# expansion.net
KiCad netlist of a schematic drawn in EAGLE
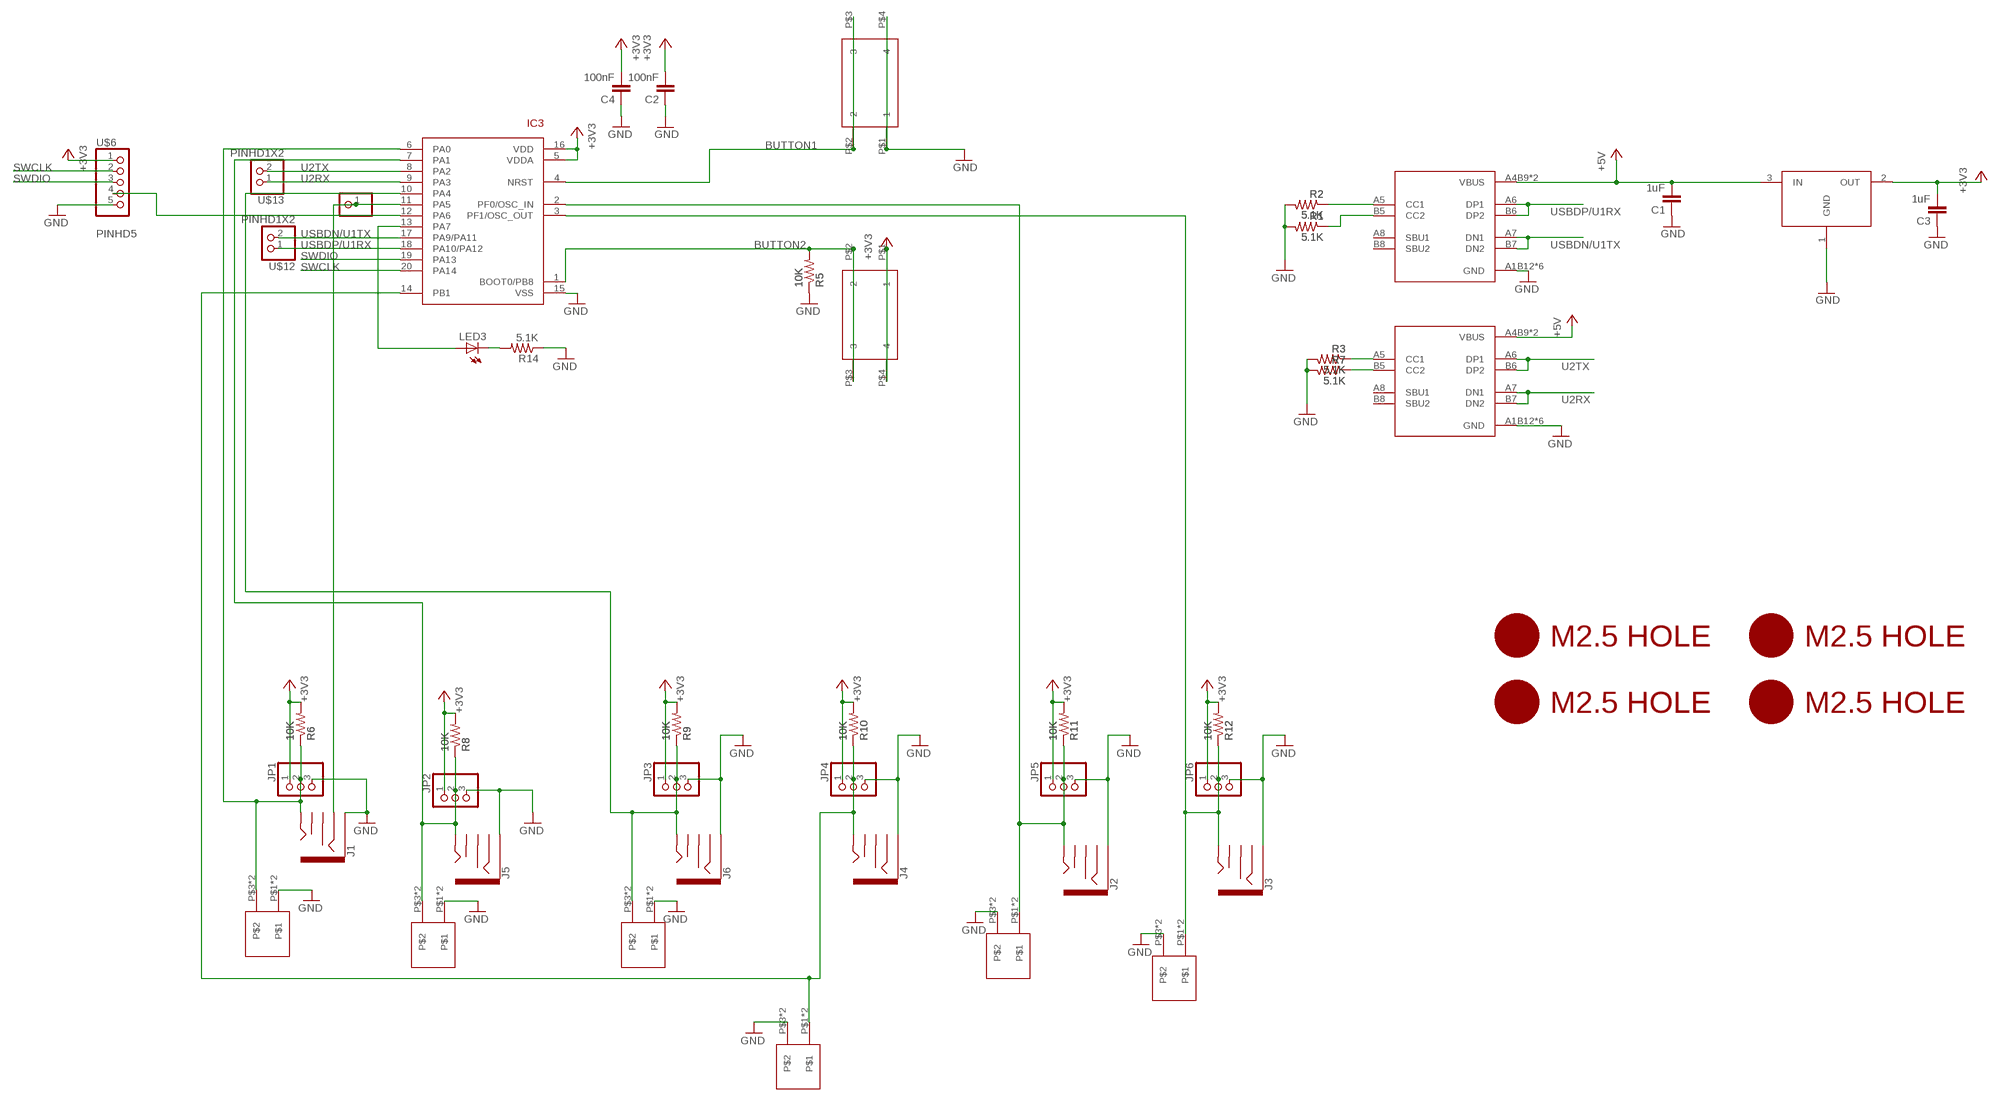
[diagram p0: schematic, sheet 1]

(export (version "E")
  (design (tool "Eeschema 10.0.6"))
  (components
    (comp (ref "C1")
      (value "1uF")
      (footprint "eagle-import:0805")
      (libsource (lib "eagle-import") (part "CAP0805"))
    )
    (comp (ref "C2")
      (value "100nF")
      (footprint "eagle-import:0805")
      (libsource (lib "eagle-import") (part "CAP0805"))
    )
    (comp (ref "C3")
      (value "1uF")
      (footprint "eagle-import:0805")
      (libsource (lib "eagle-import") (part "CAP0805"))
    )
    (comp (ref "C4")
      (value "100nF")
      (footprint "eagle-import:0805")
      (libsource (lib "eagle-import") (part "CAP0805"))
    )
    (comp (ref "IC3")
      (value "STM32F042F4")
      (footprint "eagle-import:TSSOP20")
      (libsource (lib "eagle-import") (part "STM32F042F4"))
    )
    (comp (ref "J1")
      (value "AUDIO_JACK_3.5MM_PTH")
      (footprint "eagle-import:AUDIO-JACK")
      (libsource (lib "eagle-import") (part "AUDIO_JACK_3.5MM_PTH"))
    )
    (comp (ref "J2")
      (value "AUDIO_JACK_3.5MM_PTH")
      (footprint "eagle-import:AUDIO-JACK")
      (libsource (lib "eagle-import") (part "AUDIO_JACK_3.5MM_PTH"))
    )
    (comp (ref "J3")
      (value "AUDIO_JACK_3.5MM_PTH")
      (footprint "eagle-import:AUDIO-JACK")
      (libsource (lib "eagle-import") (part "AUDIO_JACK_3.5MM_PTH"))
    )
    (comp (ref "J4")
      (value "AUDIO_JACK_3.5MM_PTH")
      (footprint "eagle-import:AUDIO-JACK")
      (libsource (lib "eagle-import") (part "AUDIO_JACK_3.5MM_PTH"))
    )
    (comp (ref "J5")
      (value "AUDIO_JACK_3.5MM_PTH")
      (footprint "eagle-import:AUDIO-JACK")
      (libsource (lib "eagle-import") (part "AUDIO_JACK_3.5MM_PTH"))
    )
    (comp (ref "J6")
      (value "AUDIO_JACK_3.5MM_PTH")
      (footprint "eagle-import:AUDIO-JACK")
      (libsource (lib "eagle-import") (part "AUDIO_JACK_3.5MM_PTH"))
    )
    (comp (ref "JP1")
      (value "PINHD-1X3")
      (footprint "eagle-import:1X03")
      (libsource (lib "eagle-import") (part "PINHD-1X3"))
    )
    (comp (ref "JP2")
      (value "PINHD-1X3")
      (footprint "eagle-import:1X03")
      (libsource (lib "eagle-import") (part "PINHD-1X3"))
    )
    (comp (ref "JP3")
      (value "PINHD-1X3")
      (footprint "eagle-import:1X03")
      (libsource (lib "eagle-import") (part "PINHD-1X3"))
    )
    (comp (ref "JP4")
      (value "PINHD-1X3")
      (footprint "eagle-import:1X03")
      (libsource (lib "eagle-import") (part "PINHD-1X3"))
    )
    (comp (ref "JP5")
      (value "PINHD-1X3")
      (footprint "eagle-import:1X03")
      (libsource (lib "eagle-import") (part "PINHD-1X3"))
    )
    (comp (ref "JP6")
      (value "PINHD-1X3")
      (footprint "eagle-import:1X03")
      (libsource (lib "eagle-import") (part "PINHD-1X3"))
    )
    (comp (ref "JP7")
      (value "PINHD-1X1CB")
      (footprint "eagle-import:1X01-CLEANBIG")
      (libsource (lib "eagle-import") (part "PINHD-1X1CB"))
    )
    (comp (ref "LED3")
      (value "LEDCHIP-LED0805")
      (footprint "eagle-import:CHIP-LED0805")
      (libsource (lib "eagle-import") (part "LEDCHIP-LED0805"))
    )
    (comp (ref "R1")
      (value "5.1K")
      (footprint "eagle-import:0805")
      (libsource (lib "eagle-import") (part "joyAnalog_RESISTOR0805-RES"))
    )
    (comp (ref "R2")
      (value "5.1K")
      (footprint "eagle-import:0805")
      (libsource (lib "eagle-import") (part "joyAnalog_RESISTOR0805-RES"))
    )
    (comp (ref "R3")
      (value "5.1K")
      (footprint "eagle-import:0805")
      (libsource (lib "eagle-import") (part "joyAnalog_RESISTOR0805-RES"))
    )
    (comp (ref "R5")
      (value "10K")
      (footprint "eagle-import:0805")
      (libsource (lib "eagle-import") (part "joyAnalog_RESISTOR0805-RES"))
    )
    (comp (ref "R6")
      (value "10K")
      (footprint "eagle-import:0805")
      (libsource (lib "eagle-import") (part "joyAnalog_RESISTOR0805-RES"))
    )
    (comp (ref "R7")
      (value "5.1K")
      (footprint "eagle-import:0805")
      (libsource (lib "eagle-import") (part "joyAnalog_RESISTOR0805-RES"))
    )
    (comp (ref "R8")
      (value "10K")
      (footprint "eagle-import:0805")
      (libsource (lib "eagle-import") (part "joyAnalog_RESISTOR0805-RES"))
    )
    (comp (ref "R9")
      (value "10K")
      (footprint "eagle-import:0805")
      (libsource (lib "eagle-import") (part "joyAnalog_RESISTOR0805-RES"))
    )
    (comp (ref "R10")
      (value "10K")
      (footprint "eagle-import:0805")
      (libsource (lib "eagle-import") (part "joyAnalog_RESISTOR0805-RES"))
    )
    (comp (ref "R11")
      (value "10K")
      (footprint "eagle-import:0805")
      (libsource (lib "eagle-import") (part "joyAnalog_RESISTOR0805-RES"))
    )
    (comp (ref "R12")
      (value "10K")
      (footprint "eagle-import:0805")
      (libsource (lib "eagle-import") (part "joyAnalog_RESISTOR0805-RES"))
    )
    (comp (ref "R14")
      (value "5.1K")
      (footprint "eagle-import:0805")
      (libsource (lib "eagle-import") (part "RESISTOR0805-RES"))
    )
    (comp (ref "SW3")
      (value "324_SW")
      (footprint "eagle-import:342_SWICH_FOOT")
      (libsource (lib "eagle-import") (part "324_SW"))
    )
    (comp (ref "SW4")
      (value "324_SW")
      (footprint "eagle-import:342_SWICH_FOOT")
      (libsource (lib "eagle-import") (part "324_SW"))
    )
    (comp (ref "U$1")
      (value "DG2204R-2")
      (footprint "eagle-import:DG2204R-2")
      (libsource (lib "eagle-import") (part "DG2204R-2"))
    )
    (comp (ref "U$2")
      (value "DG2204R-2")
      (footprint "eagle-import:DG2204R-2")
      (libsource (lib "eagle-import") (part "DG2204R-2"))
    )
    (comp (ref "U$3")
      (value "DG2204R-2")
      (footprint "eagle-import:DG2204R-2")
      (libsource (lib "eagle-import") (part "DG2204R-2"))
    )
    (comp (ref "U$4")
      (value "DG2204R-2")
      (footprint "eagle-import:DG2204R-2")
      (libsource (lib "eagle-import") (part "DG2204R-2"))
    )
    (comp (ref "U$5")
      (value "DG2204R-2")
      (footprint "eagle-import:DG2204R-2")
      (libsource (lib "eagle-import") (part "DG2204R-2"))
    )
    (comp (ref "U$6")
      (value "PINHD5")
      (footprint "eagle-import:1X05")
      (libsource (lib "eagle-import") (part "PINHD5"))
    )
    (comp (ref "U$7")
      (value "DG2204R-2")
      (footprint "eagle-import:DG2204R-2")
      (libsource (lib "eagle-import") (part "DG2204R-2"))
    )
    (comp (ref "U$8")
      (value "M2.5HOLE")
      (footprint "eagle-import:M2.5HOLE")
      (libsource (lib "eagle-import") (part "M2.5HOLE"))
    )
    (comp (ref "U$9")
      (value "M2.5HOLE")
      (footprint "eagle-import:M2.5HOLE")
      (libsource (lib "eagle-import") (part "M2.5HOLE"))
    )
    (comp (ref "U$10")
      (value "M2.5HOLE")
      (footprint "eagle-import:M2.5HOLE")
      (libsource (lib "eagle-import") (part "M2.5HOLE"))
    )
    (comp (ref "U$11")
      (value "M2.5HOLE")
      (footprint "eagle-import:M2.5HOLE")
      (libsource (lib "eagle-import") (part "M2.5HOLE"))
    )
    (comp (ref "U$12")
      (value "PINHD1X2")
      (footprint "eagle-import:1X02")
      (libsource (lib "eagle-import") (part "PINHD1X2"))
    )
    (comp (ref "U$13")
      (value "PINHD1X2")
      (footprint "eagle-import:1X02")
      (libsource (lib "eagle-import") (part "PINHD1X2"))
    )
    (comp (ref "U1")
      (value "USBC_16P")
      (footprint "eagle-import:USBC_16P_FOOT")
      (libsource (lib "eagle-import") (part "USBC_16P"))
    )
    (comp (ref "U2")
      (value "USBC_16P")
      (footprint "eagle-import:USBC_16P_FOOT")
      (libsource (lib "eagle-import") (part "USBC_16P"))
    )
    (comp (ref "U4")
      (value "XC6206_DEV")
      (footprint "eagle-import:SOT23R_INFINEON")
      (libsource (lib "eagle-import") (part "XC6206_DEV"))
    )
  )
  (nets
    (net (code "1") (name "+3V3") (class "Default")
      (node (ref "C2") (pin "2") (pinfunction "2_2") (pintype "passive"))
      (node (ref "C3") (pin "2") (pinfunction "2_2") (pintype "passive"))
      (node (ref "C4") (pin "2") (pinfunction "2_2") (pintype "passive"))
      (node (ref "IC3") (pin "16") (pinfunction "VDD_16") (pintype "bidirectional"))
      (node (ref "IC3") (pin "5") (pinfunction "VDDA_5") (pintype "bidirectional"))
      (node (ref "JP1") (pin "1") (pinfunction "1_1") (pintype "passive"))
      (node (ref "JP2") (pin "1") (pinfunction "1_1") (pintype "passive"))
      (node (ref "JP3") (pin "1") (pinfunction "1_1") (pintype "passive"))
      (node (ref "JP4") (pin "1") (pinfunction "1_1") (pintype "passive"))
      (node (ref "JP5") (pin "1") (pinfunction "1_1") (pintype "passive"))
      (node (ref "JP6") (pin "1") (pinfunction "1_1") (pintype "passive"))
      (node (ref "R10") (pin "2") (pinfunction "2_2") (pintype "passive"))
      (node (ref "R11") (pin "2") (pinfunction "2_2") (pintype "passive"))
      (node (ref "R12") (pin "2") (pinfunction "2_2") (pintype "passive"))
      (node (ref "R6") (pin "2") (pinfunction "2_2") (pintype "passive"))
      (node (ref "R8") (pin "2") (pinfunction "2_2") (pintype "passive"))
      (node (ref "R9") (pin "2") (pinfunction "2_2") (pintype "passive"))
      (node (ref "SW4") (pin "P$1") (pinfunction "1_P$1") (pintype "bidirectional"))
      (node (ref "SW4") (pin "P$4") (pinfunction "4_P$4") (pintype "bidirectional"))
      (node (ref "U$6") (pin "1") (pinfunction "1_1") (pintype "passive"))
      (node (ref "U4") (pin "2") (pinfunction "OUT_2") (pintype "bidirectional"))
    )
    (net (code "2") (name "+5V") (class "Default")
      (node (ref "C1") (pin "2") (pinfunction "2_2") (pintype "passive"))
      (node (ref "U1") (pin "A4B9") (pinfunction "VBUS_A4B9") (pintype "bidirectional"))
      (node (ref "U1") (pin "B4A9") (pinfunction "VBUS_B4A9") (pintype "bidirectional"))
      (node (ref "U2") (pin "A4B9") (pinfunction "VBUS_A4B9") (pintype "bidirectional"))
      (node (ref "U2") (pin "B4A9") (pinfunction "VBUS_B4A9") (pintype "bidirectional"))
      (node (ref "U4") (pin "3") (pinfunction "IN_3") (pintype "bidirectional"))
    )
    (net (code "3") (name "/BUTTON1") (class "Default")
      (node (ref "IC3") (pin "4") (pinfunction "NRST_4") (pintype "bidirectional"))
      (node (ref "SW3") (pin "P$2") (pinfunction "2_P$2") (pintype "bidirectional"))
      (node (ref "SW3") (pin "P$3") (pinfunction "3_P$3") (pintype "bidirectional"))
    )
    (net (code "4") (name "/BUTTON2") (class "Default")
      (node (ref "IC3") (pin "1") (pinfunction "BOOT0/PB8_1") (pintype "bidirectional"))
      (node (ref "R5") (pin "2") (pinfunction "2_2") (pintype "passive"))
      (node (ref "SW4") (pin "P$2") (pinfunction "2_P$2") (pintype "bidirectional"))
      (node (ref "SW4") (pin "P$3") (pinfunction "3_P$3") (pintype "bidirectional"))
    )
    (net (code "5") (name "/SWCLK") (class "Default")
      (node (ref "IC3") (pin "20") (pinfunction "PA14_20") (pintype "bidirectional"))
      (node (ref "U$6") (pin "2") (pinfunction "2_2") (pintype "passive"))
    )
    (net (code "6") (name "/SWDIO") (class "Default")
      (node (ref "IC3") (pin "19") (pinfunction "PA13_19") (pintype "bidirectional"))
      (node (ref "U$6") (pin "3") (pinfunction "3_3") (pintype "passive"))
    )
    (net (code "7") (name "/U2RX") (class "Default")
      (node (ref "IC3") (pin "9") (pinfunction "PA3_9") (pintype "bidirectional"))
      (node (ref "U$13") (pin "1") (pinfunction "1_1") (pintype "passive"))
      (node (ref "U1") (pin "A7") (pinfunction "DN1_A7") (pintype "bidirectional"))
      (node (ref "U1") (pin "B7") (pinfunction "DN2_B7") (pintype "bidirectional"))
    )
    (net (code "8") (name "/U2TX") (class "Default")
      (node (ref "IC3") (pin "8") (pinfunction "PA2_8") (pintype "bidirectional"))
      (node (ref "U$13") (pin "2") (pinfunction "2_2") (pintype "passive"))
      (node (ref "U1") (pin "A6") (pinfunction "DP1_A6") (pintype "bidirectional"))
      (node (ref "U1") (pin "B6") (pinfunction "DP2_B6") (pintype "bidirectional"))
    )
    (net (code "9") (name "/USBDN{slash}U1TX") (class "Default")
      (node (ref "IC3") (pin "17") (pinfunction "PA9/PA11_17") (pintype "bidirectional"))
      (node (ref "U$12") (pin "2") (pinfunction "2_2") (pintype "passive"))
      (node (ref "U2") (pin "A7") (pinfunction "DN1_A7") (pintype "bidirectional"))
      (node (ref "U2") (pin "B7") (pinfunction "DN2_B7") (pintype "bidirectional"))
    )
    (net (code "10") (name "/USBDP{slash}U1RX") (class "Default")
      (node (ref "IC3") (pin "18") (pinfunction "PA10/PA12_18") (pintype "bidirectional"))
      (node (ref "U$12") (pin "1") (pinfunction "1_1") (pintype "passive"))
      (node (ref "U2") (pin "A6") (pinfunction "DP1_A6") (pintype "bidirectional"))
      (node (ref "U2") (pin "B6") (pinfunction "DP2_B6") (pintype "bidirectional"))
    )
    (net (code "11") (name "GND") (class "Default")
      (node (ref "C1") (pin "1") (pinfunction "1_1") (pintype "passive"))
      (node (ref "C2") (pin "1") (pinfunction "1_1") (pintype "passive"))
      (node (ref "C3") (pin "1") (pinfunction "1_1") (pintype "passive"))
      (node (ref "C4") (pin "1") (pinfunction "1_1") (pintype "passive"))
      (node (ref "IC3") (pin "15") (pinfunction "VSS_15") (pintype "bidirectional"))
      (node (ref "J1") (pin "SLEEVE") (pinfunction "SLEEVE_SLEEVE") (pintype "bidirectional"))
      (node (ref "J2") (pin "SLEEVE") (pinfunction "SLEEVE_SLEEVE") (pintype "bidirectional"))
      (node (ref "J3") (pin "SLEEVE") (pinfunction "SLEEVE_SLEEVE") (pintype "bidirectional"))
      (node (ref "J4") (pin "SLEEVE") (pinfunction "SLEEVE_SLEEVE") (pintype "bidirectional"))
      (node (ref "J5") (pin "SLEEVE") (pinfunction "SLEEVE_SLEEVE") (pintype "bidirectional"))
      (node (ref "J6") (pin "SLEEVE") (pinfunction "SLEEVE_SLEEVE") (pintype "bidirectional"))
      (node (ref "JP1") (pin "3") (pinfunction "3_3") (pintype "passive"))
      (node (ref "JP2") (pin "3") (pinfunction "3_3") (pintype "passive"))
      (node (ref "JP3") (pin "3") (pinfunction "3_3") (pintype "passive"))
      (node (ref "JP4") (pin "3") (pinfunction "3_3") (pintype "passive"))
      (node (ref "JP5") (pin "3") (pinfunction "3_3") (pintype "passive"))
      (node (ref "JP6") (pin "3") (pinfunction "3_3") (pintype "passive"))
      (node (ref "R1") (pin "2") (pinfunction "2_2") (pintype "passive"))
      (node (ref "R14") (pin "1") (pinfunction "1_1") (pintype "passive"))
      (node (ref "R2") (pin "2") (pinfunction "2_2") (pintype "passive"))
      (node (ref "R3") (pin "2") (pinfunction "2_2") (pintype "passive"))
      (node (ref "R5") (pin "1") (pinfunction "1_1") (pintype "passive"))
      (node (ref "R7") (pin "2") (pinfunction "2_2") (pintype "passive"))
      (node (ref "SW3") (pin "P$1") (pinfunction "1_P$1") (pintype "bidirectional"))
      (node (ref "SW3") (pin "P$4") (pinfunction "4_P$4") (pintype "bidirectional"))
      (node (ref "U$1") (pin "P$3") (pinfunction "P$2_P$3") (pintype "bidirectional"))
      (node (ref "U$1") (pin "P$4") (pinfunction "P$2_P$4") (pintype "bidirectional"))
      (node (ref "U$2") (pin "P$3") (pinfunction "P$2_P$3") (pintype "bidirectional"))
      (node (ref "U$2") (pin "P$4") (pinfunction "P$2_P$4") (pintype "bidirectional"))
      (node (ref "U$3") (pin "P$3") (pinfunction "P$2_P$3") (pintype "bidirectional"))
      (node (ref "U$3") (pin "P$4") (pinfunction "P$2_P$4") (pintype "bidirectional"))
      (node (ref "U$4") (pin "P$1") (pinfunction "P$1_P$1") (pintype "bidirectional"))
      (node (ref "U$4") (pin "P$2") (pinfunction "P$1_P$2") (pintype "bidirectional"))
      (node (ref "U$5") (pin "P$1") (pinfunction "P$1_P$1") (pintype "bidirectional"))
      (node (ref "U$5") (pin "P$2") (pinfunction "P$1_P$2") (pintype "bidirectional"))
      (node (ref "U$6") (pin "5") (pinfunction "5_5") (pintype "passive"))
      (node (ref "U$7") (pin "P$1") (pinfunction "P$1_P$1") (pintype "bidirectional"))
      (node (ref "U$7") (pin "P$2") (pinfunction "P$1_P$2") (pintype "bidirectional"))
      (node (ref "U1") (pin "A1B12") (pinfunction "GND_A1B12") (pintype "bidirectional"))
      (node (ref "U1") (pin "B11A12") (pinfunction "GND_B11A12") (pintype "bidirectional"))
      (node (ref "U1") (pin "P$13") (pinfunction "GND_P$13") (pintype "bidirectional"))
      (node (ref "U1") (pin "P$14") (pinfunction "GND_P$14") (pintype "bidirectional"))
      (node (ref "U1") (pin "P$15") (pinfunction "GND_P$15") (pintype "bidirectional"))
      (node (ref "U1") (pin "P$16") (pinfunction "GND_P$16") (pintype "bidirectional"))
      (node (ref "U2") (pin "A1B12") (pinfunction "GND_A1B12") (pintype "bidirectional"))
      (node (ref "U2") (pin "B11A12") (pinfunction "GND_B11A12") (pintype "bidirectional"))
      (node (ref "U2") (pin "P$13") (pinfunction "GND_P$13") (pintype "bidirectional"))
      (node (ref "U2") (pin "P$14") (pinfunction "GND_P$14") (pintype "bidirectional"))
      (node (ref "U2") (pin "P$15") (pinfunction "GND_P$15") (pintype "bidirectional"))
      (node (ref "U2") (pin "P$16") (pinfunction "GND_P$16") (pintype "bidirectional"))
      (node (ref "U4") (pin "1") (pinfunction "GND_1") (pintype "bidirectional"))
    )
    (net (code "12") (name "Net-(IC3-PA0)") (class "Default")
      (node (ref "IC3") (pin "6") (pinfunction "PA0_6") (pintype "bidirectional"))
      (node (ref "J1") (pin "TIP") (pinfunction "TIP_TIP") (pintype "bidirectional"))
      (node (ref "JP1") (pin "2") (pinfunction "2_2") (pintype "passive"))
      (node (ref "R6") (pin "1") (pinfunction "1_1") (pintype "passive"))
      (node (ref "U$4") (pin "P$3") (pinfunction "P$2_P$3") (pintype "bidirectional"))
      (node (ref "U$4") (pin "P$4") (pinfunction "P$2_P$4") (pintype "bidirectional"))
    )
    (net (code "13") (name "Net-(IC3-PA1)") (class "Default")
      (node (ref "IC3") (pin "7") (pinfunction "PA1_7") (pintype "bidirectional"))
      (node (ref "J5") (pin "TIP") (pinfunction "TIP_TIP") (pintype "bidirectional"))
      (node (ref "JP2") (pin "2") (pinfunction "2_2") (pintype "passive"))
      (node (ref "R8") (pin "1") (pinfunction "1_1") (pintype "passive"))
      (node (ref "U$5") (pin "P$3") (pinfunction "P$2_P$3") (pintype "bidirectional"))
      (node (ref "U$5") (pin "P$4") (pinfunction "P$2_P$4") (pintype "bidirectional"))
    )
    (net (code "14") (name "Net-(IC3-PA4)") (class "Default")
      (node (ref "IC3") (pin "10") (pinfunction "PA4_10") (pintype "bidirectional"))
      (node (ref "J6") (pin "TIP") (pinfunction "TIP_TIP") (pintype "bidirectional"))
      (node (ref "JP3") (pin "2") (pinfunction "2_2") (pintype "passive"))
      (node (ref "R9") (pin "1") (pinfunction "1_1") (pintype "passive"))
      (node (ref "U$7") (pin "P$3") (pinfunction "P$2_P$3") (pintype "bidirectional"))
      (node (ref "U$7") (pin "P$4") (pinfunction "P$2_P$4") (pintype "bidirectional"))
    )
    (net (code "15") (name "Net-(IC3-PA5)") (class "Default")
      (node (ref "IC3") (pin "11") (pinfunction "PA5_11") (pintype "bidirectional"))
      (node (ref "J1") (pin "RING") (pinfunction "RING_RING") (pintype "bidirectional"))
      (node (ref "JP7") (pin "1") (pinfunction "1_1") (pintype "passive"))
    )
    (net (code "16") (name "Net-(IC3-PA6)") (class "Default")
      (node (ref "IC3") (pin "12") (pinfunction "PA6_12") (pintype "bidirectional"))
      (node (ref "U$6") (pin "4") (pinfunction "4_4") (pintype "passive"))
    )
    (net (code "17") (name "Net-(IC3-PA7)") (class "Default")
      (node (ref "IC3") (pin "13") (pinfunction "PA7_13") (pintype "bidirectional"))
      (node (ref "LED3") (pin "A") (pinfunction "A_A") (pintype "passive"))
    )
    (net (code "18") (name "Net-(IC3-PB1)") (class "Default")
      (node (ref "IC3") (pin "14") (pinfunction "PB1_14") (pintype "bidirectional"))
      (node (ref "J4") (pin "TIP") (pinfunction "TIP_TIP") (pintype "bidirectional"))
      (node (ref "JP4") (pin "2") (pinfunction "2_2") (pintype "passive"))
      (node (ref "R10") (pin "1") (pinfunction "1_1") (pintype "passive"))
      (node (ref "U$1") (pin "P$1") (pinfunction "P$1_P$1") (pintype "bidirectional"))
      (node (ref "U$1") (pin "P$2") (pinfunction "P$1_P$2") (pintype "bidirectional"))
    )
    (net (code "19") (name "Net-(IC3-PF0{slash}OSC_IN)") (class "Default")
      (node (ref "IC3") (pin "2") (pinfunction "PF0/OSC_IN_2") (pintype "bidirectional"))
      (node (ref "J2") (pin "TIP") (pinfunction "TIP_TIP") (pintype "bidirectional"))
      (node (ref "JP5") (pin "2") (pinfunction "2_2") (pintype "passive"))
      (node (ref "R11") (pin "1") (pinfunction "1_1") (pintype "passive"))
      (node (ref "U$2") (pin "P$1") (pinfunction "P$1_P$1") (pintype "bidirectional"))
      (node (ref "U$2") (pin "P$2") (pinfunction "P$1_P$2") (pintype "bidirectional"))
    )
    (net (code "20") (name "Net-(IC3-PF1{slash}OSC_OUT)") (class "Default")
      (node (ref "IC3") (pin "3") (pinfunction "PF1/OSC_OUT_3") (pintype "bidirectional"))
      (node (ref "J3") (pin "TIP") (pinfunction "TIP_TIP") (pintype "bidirectional"))
      (node (ref "JP6") (pin "2") (pinfunction "2_2") (pintype "passive"))
      (node (ref "R12") (pin "1") (pinfunction "1_1") (pintype "passive"))
      (node (ref "U$3") (pin "P$1") (pinfunction "P$1_P$1") (pintype "bidirectional"))
      (node (ref "U$3") (pin "P$2") (pinfunction "P$1_P$2") (pintype "bidirectional"))
    )
    (net (code "21") (name "Net-(LED3-PadC)") (class "Default")
      (node (ref "LED3") (pin "C") (pinfunction "C_C") (pintype "passive"))
      (node (ref "R14") (pin "2") (pinfunction "2_2") (pintype "passive"))
    )
    (net (code "22") (name "Net-(U1-CC1)") (class "Default")
      (node (ref "R3") (pin "1") (pinfunction "1_1") (pintype "passive"))
      (node (ref "U1") (pin "A5") (pinfunction "CC1_A5") (pintype "bidirectional"))
    )
    (net (code "23") (name "Net-(U1-CC2)") (class "Default")
      (node (ref "R7") (pin "1") (pinfunction "1_1") (pintype "passive"))
      (node (ref "U1") (pin "B5") (pinfunction "CC2_B5") (pintype "bidirectional"))
    )
    (net (code "24") (name "Net-(U2-CC1)") (class "Default")
      (node (ref "R2") (pin "1") (pinfunction "1_1") (pintype "passive"))
      (node (ref "U2") (pin "A5") (pinfunction "CC1_A5") (pintype "bidirectional"))
    )
    (net (code "25") (name "Net-(U2-CC2)") (class "Default")
      (node (ref "R1") (pin "1") (pinfunction "1_1") (pintype "passive"))
      (node (ref "U2") (pin "B5") (pinfunction "CC2_B5") (pintype "bidirectional"))
    )
    (net (code "26") (name "unconnected-(J1-PadRSH)") (class "Default")
      (node (ref "J1") (pin "RSH") (pinfunction "RSH_RSH") (pintype "bidirectional"))
    )
    (net (code "27") (name "unconnected-(J1-PadTSH)") (class "Default")
      (node (ref "J1") (pin "TSH") (pinfunction "TSH_TSH") (pintype "bidirectional"))
    )
    (net (code "28") (name "unconnected-(J2-PadRING)") (class "Default")
      (node (ref "J2") (pin "RING") (pinfunction "RING_RING") (pintype "bidirectional"))
    )
    (net (code "29") (name "unconnected-(J2-PadRSH)") (class "Default")
      (node (ref "J2") (pin "RSH") (pinfunction "RSH_RSH") (pintype "bidirectional"))
    )
    (net (code "30") (name "unconnected-(J2-PadTSH)") (class "Default")
      (node (ref "J2") (pin "TSH") (pinfunction "TSH_TSH") (pintype "bidirectional"))
    )
    (net (code "31") (name "unconnected-(J3-PadRING)") (class "Default")
      (node (ref "J3") (pin "RING") (pinfunction "RING_RING") (pintype "bidirectional"))
    )
    (net (code "32") (name "unconnected-(J3-PadRSH)") (class "Default")
      (node (ref "J3") (pin "RSH") (pinfunction "RSH_RSH") (pintype "bidirectional"))
    )
    (net (code "33") (name "unconnected-(J3-PadTSH)") (class "Default")
      (node (ref "J3") (pin "TSH") (pinfunction "TSH_TSH") (pintype "bidirectional"))
    )
    (net (code "34") (name "unconnected-(J4-PadRING)") (class "Default")
      (node (ref "J4") (pin "RING") (pinfunction "RING_RING") (pintype "bidirectional"))
    )
    (net (code "35") (name "unconnected-(J4-PadRSH)") (class "Default")
      (node (ref "J4") (pin "RSH") (pinfunction "RSH_RSH") (pintype "bidirectional"))
    )
    (net (code "36") (name "unconnected-(J4-PadTSH)") (class "Default")
      (node (ref "J4") (pin "TSH") (pinfunction "TSH_TSH") (pintype "bidirectional"))
    )
    (net (code "37") (name "unconnected-(J5-PadRING)") (class "Default")
      (node (ref "J5") (pin "RING") (pinfunction "RING_RING") (pintype "bidirectional"))
    )
    (net (code "38") (name "unconnected-(J5-PadRSH)") (class "Default")
      (node (ref "J5") (pin "RSH") (pinfunction "RSH_RSH") (pintype "bidirectional"))
    )
    (net (code "39") (name "unconnected-(J5-PadTSH)") (class "Default")
      (node (ref "J5") (pin "TSH") (pinfunction "TSH_TSH") (pintype "bidirectional"))
    )
    (net (code "40") (name "unconnected-(J6-PadRING)") (class "Default")
      (node (ref "J6") (pin "RING") (pinfunction "RING_RING") (pintype "bidirectional"))
    )
    (net (code "41") (name "unconnected-(J6-PadRSH)") (class "Default")
      (node (ref "J6") (pin "RSH") (pinfunction "RSH_RSH") (pintype "bidirectional"))
    )
    (net (code "42") (name "unconnected-(J6-PadTSH)") (class "Default")
      (node (ref "J6") (pin "TSH") (pinfunction "TSH_TSH") (pintype "bidirectional"))
    )
    (net (code "43") (name "unconnected-(U1-SBU1-PadA8)") (class "Default")
      (node (ref "U1") (pin "A8") (pinfunction "SBU1_A8") (pintype "bidirectional"))
    )
    (net (code "44") (name "unconnected-(U1-SBU2-PadB8)") (class "Default")
      (node (ref "U1") (pin "B8") (pinfunction "SBU2_B8") (pintype "bidirectional"))
    )
    (net (code "45") (name "unconnected-(U2-SBU1-PadA8)") (class "Default")
      (node (ref "U2") (pin "A8") (pinfunction "SBU1_A8") (pintype "bidirectional"))
    )
    (net (code "46") (name "unconnected-(U2-SBU2-PadB8)") (class "Default")
      (node (ref "U2") (pin "B8") (pinfunction "SBU2_B8") (pintype "bidirectional"))
    )
  )
)
